# USB.net
KiCad netlist of a schematic drawn in EAGLE
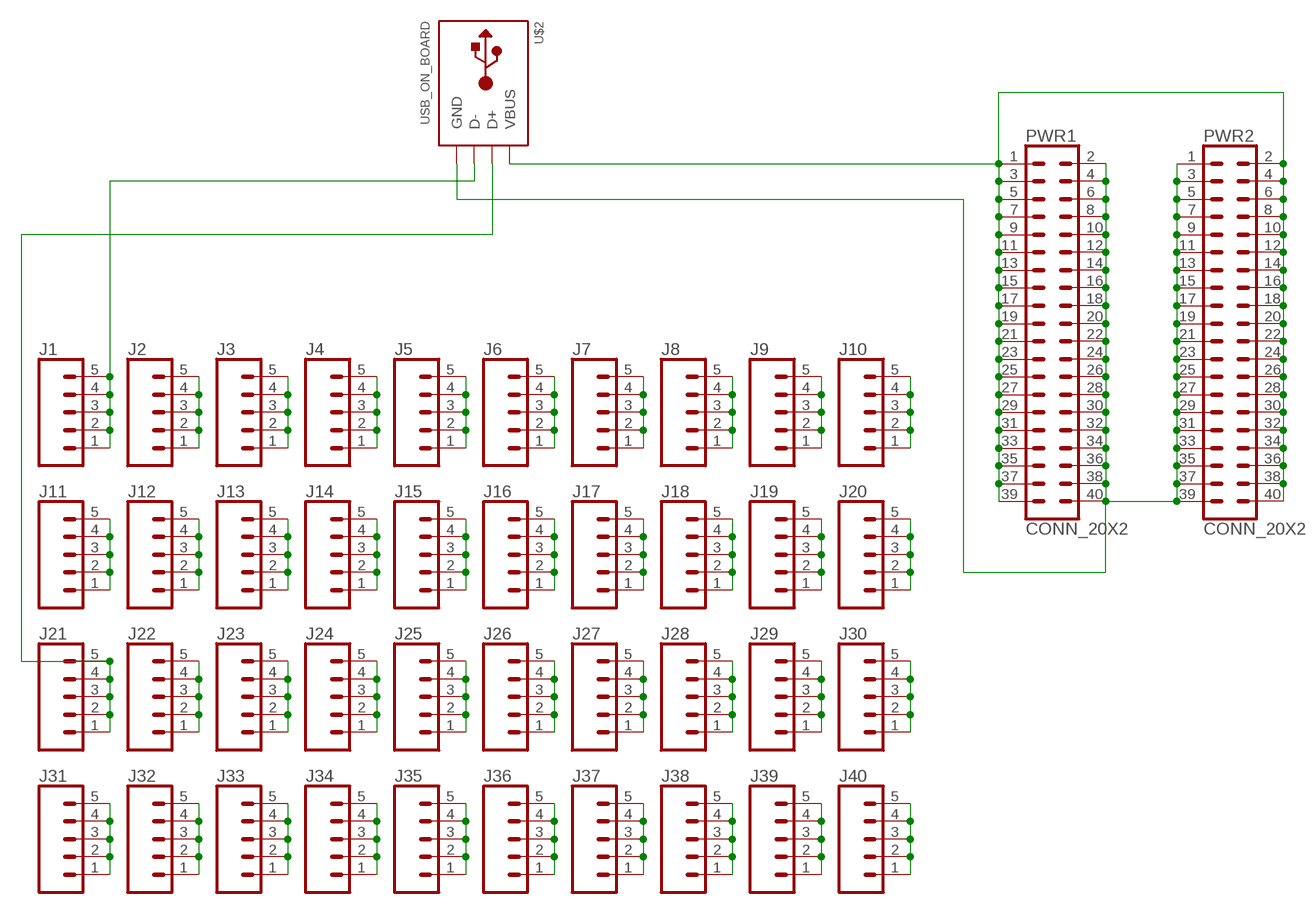
[diagram p0: schematic, sheet 1]

(export (version "E")
  (design (tool "Eeschema 10.0.6"))
  (components
    (comp (ref "J1")
      (value "CONN_05")
      (footprint "eagle-import:1X05")
      (libsource (lib "eagle-import") (part "CONN_05"))
    )
    (comp (ref "J2")
      (value "CONN_05")
      (footprint "eagle-import:1X05")
      (libsource (lib "eagle-import") (part "CONN_05"))
    )
    (comp (ref "J3")
      (value "CONN_05")
      (footprint "eagle-import:1X05")
      (libsource (lib "eagle-import") (part "CONN_05"))
    )
    (comp (ref "J4")
      (value "CONN_05")
      (footprint "eagle-import:1X05")
      (libsource (lib "eagle-import") (part "CONN_05"))
    )
    (comp (ref "J5")
      (value "CONN_05")
      (footprint "eagle-import:1X05")
      (libsource (lib "eagle-import") (part "CONN_05"))
    )
    (comp (ref "J6")
      (value "CONN_05")
      (footprint "eagle-import:1X05")
      (libsource (lib "eagle-import") (part "CONN_05"))
    )
    (comp (ref "J7")
      (value "CONN_05")
      (footprint "eagle-import:1X05")
      (libsource (lib "eagle-import") (part "CONN_05"))
    )
    (comp (ref "J8")
      (value "CONN_05")
      (footprint "eagle-import:1X05")
      (libsource (lib "eagle-import") (part "CONN_05"))
    )
    (comp (ref "J9")
      (value "CONN_05")
      (footprint "eagle-import:1X05")
      (libsource (lib "eagle-import") (part "CONN_05"))
    )
    (comp (ref "J10")
      (value "CONN_05")
      (footprint "eagle-import:1X05")
      (libsource (lib "eagle-import") (part "CONN_05"))
    )
    (comp (ref "J11")
      (value "CONN_05")
      (footprint "eagle-import:1X05")
      (libsource (lib "eagle-import") (part "CONN_05"))
    )
    (comp (ref "J12")
      (value "CONN_05")
      (footprint "eagle-import:1X05")
      (libsource (lib "eagle-import") (part "CONN_05"))
    )
    (comp (ref "J13")
      (value "CONN_05")
      (footprint "eagle-import:1X05")
      (libsource (lib "eagle-import") (part "CONN_05"))
    )
    (comp (ref "J14")
      (value "CONN_05")
      (footprint "eagle-import:1X05")
      (libsource (lib "eagle-import") (part "CONN_05"))
    )
    (comp (ref "J15")
      (value "CONN_05")
      (footprint "eagle-import:1X05")
      (libsource (lib "eagle-import") (part "CONN_05"))
    )
    (comp (ref "J16")
      (value "CONN_05")
      (footprint "eagle-import:1X05")
      (libsource (lib "eagle-import") (part "CONN_05"))
    )
    (comp (ref "J17")
      (value "CONN_05")
      (footprint "eagle-import:1X05")
      (libsource (lib "eagle-import") (part "CONN_05"))
    )
    (comp (ref "J18")
      (value "CONN_05")
      (footprint "eagle-import:1X05")
      (libsource (lib "eagle-import") (part "CONN_05"))
    )
    (comp (ref "J19")
      (value "CONN_05")
      (footprint "eagle-import:1X05")
      (libsource (lib "eagle-import") (part "CONN_05"))
    )
    (comp (ref "J20")
      (value "CONN_05")
      (footprint "eagle-import:1X05")
      (libsource (lib "eagle-import") (part "CONN_05"))
    )
    (comp (ref "J21")
      (value "CONN_05")
      (footprint "eagle-import:1X05")
      (libsource (lib "eagle-import") (part "CONN_05"))
    )
    (comp (ref "J22")
      (value "CONN_05")
      (footprint "eagle-import:1X05")
      (libsource (lib "eagle-import") (part "CONN_05"))
    )
    (comp (ref "J23")
      (value "CONN_05")
      (footprint "eagle-import:1X05")
      (libsource (lib "eagle-import") (part "CONN_05"))
    )
    (comp (ref "J24")
      (value "CONN_05")
      (footprint "eagle-import:1X05")
      (libsource (lib "eagle-import") (part "CONN_05"))
    )
    (comp (ref "J25")
      (value "CONN_05")
      (footprint "eagle-import:1X05")
      (libsource (lib "eagle-import") (part "CONN_05"))
    )
    (comp (ref "J26")
      (value "CONN_05")
      (footprint "eagle-import:1X05")
      (libsource (lib "eagle-import") (part "CONN_05"))
    )
    (comp (ref "J27")
      (value "CONN_05")
      (footprint "eagle-import:1X05")
      (libsource (lib "eagle-import") (part "CONN_05"))
    )
    (comp (ref "J28")
      (value "CONN_05")
      (footprint "eagle-import:1X05")
      (libsource (lib "eagle-import") (part "CONN_05"))
    )
    (comp (ref "J29")
      (value "CONN_05")
      (footprint "eagle-import:1X05")
      (libsource (lib "eagle-import") (part "CONN_05"))
    )
    (comp (ref "J30")
      (value "CONN_05")
      (footprint "eagle-import:1X05")
      (libsource (lib "eagle-import") (part "CONN_05"))
    )
    (comp (ref "J31")
      (value "CONN_05")
      (footprint "eagle-import:1X05")
      (libsource (lib "eagle-import") (part "CONN_05"))
    )
    (comp (ref "J32")
      (value "CONN_05")
      (footprint "eagle-import:1X05")
      (libsource (lib "eagle-import") (part "CONN_05"))
    )
    (comp (ref "J33")
      (value "CONN_05")
      (footprint "eagle-import:1X05")
      (libsource (lib "eagle-import") (part "CONN_05"))
    )
    (comp (ref "J34")
      (value "CONN_05")
      (footprint "eagle-import:1X05")
      (libsource (lib "eagle-import") (part "CONN_05"))
    )
    (comp (ref "J35")
      (value "CONN_05")
      (footprint "eagle-import:1X05")
      (libsource (lib "eagle-import") (part "CONN_05"))
    )
    (comp (ref "J36")
      (value "CONN_05")
      (footprint "eagle-import:1X05")
      (libsource (lib "eagle-import") (part "CONN_05"))
    )
    (comp (ref "J37")
      (value "CONN_05")
      (footprint "eagle-import:1X05")
      (libsource (lib "eagle-import") (part "CONN_05"))
    )
    (comp (ref "J38")
      (value "CONN_05")
      (footprint "eagle-import:1X05")
      (libsource (lib "eagle-import") (part "CONN_05"))
    )
    (comp (ref "J39")
      (value "CONN_05")
      (footprint "eagle-import:1X05")
      (libsource (lib "eagle-import") (part "CONN_05"))
    )
    (comp (ref "J40")
      (value "CONN_05")
      (footprint "eagle-import:1X05")
      (libsource (lib "eagle-import") (part "CONN_05"))
    )
    (comp (ref "PWR1")
      (value "CONN_20X2")
      (footprint "eagle-import:2X20")
      (libsource (lib "eagle-import") (part "CONN_20X2"))
    )
    (comp (ref "PWR2")
      (value "CONN_20X2")
      (footprint "eagle-import:2X20")
      (libsource (lib "eagle-import") (part "CONN_20X2"))
    )
    (comp (ref "U$2")
      (value "USB_ON_BOARD")
      (footprint "eagle-import:USB_ON_BOARD")
      (libsource (lib "eagle-import") (part "USB_ON_BOARD"))
    )
  )
  (nets
    (net (code "1") (name "Net-(J1-Pad1)") (class "Default")
      (node (ref "J1") (pin "1") (pinfunction "1_1") (pintype "passive"))
      (node (ref "J1") (pin "2") (pinfunction "2_2") (pintype "passive"))
      (node (ref "J1") (pin "3") (pinfunction "3_3") (pintype "passive"))
      (node (ref "J1") (pin "4") (pinfunction "4_4") (pintype "passive"))
      (node (ref "J1") (pin "5") (pinfunction "5_5") (pintype "passive"))
      (node (ref "U$2") (pin "D-") (pinfunction "D-_D-") (pintype "bidirectional"))
    )
    (net (code "2") (name "Net-(J2-Pad1)") (class "Default")
      (node (ref "J2") (pin "1") (pinfunction "1_1") (pintype "passive"))
      (node (ref "J2") (pin "2") (pinfunction "2_2") (pintype "passive"))
      (node (ref "J2") (pin "3") (pinfunction "3_3") (pintype "passive"))
      (node (ref "J2") (pin "4") (pinfunction "4_4") (pintype "passive"))
      (node (ref "J2") (pin "5") (pinfunction "5_5") (pintype "passive"))
    )
    (net (code "3") (name "Net-(J3-Pad1)") (class "Default")
      (node (ref "J3") (pin "1") (pinfunction "1_1") (pintype "passive"))
      (node (ref "J3") (pin "2") (pinfunction "2_2") (pintype "passive"))
      (node (ref "J3") (pin "3") (pinfunction "3_3") (pintype "passive"))
      (node (ref "J3") (pin "4") (pinfunction "4_4") (pintype "passive"))
      (node (ref "J3") (pin "5") (pinfunction "5_5") (pintype "passive"))
    )
    (net (code "4") (name "Net-(J4-Pad1)") (class "Default")
      (node (ref "J4") (pin "1") (pinfunction "1_1") (pintype "passive"))
      (node (ref "J4") (pin "2") (pinfunction "2_2") (pintype "passive"))
      (node (ref "J4") (pin "3") (pinfunction "3_3") (pintype "passive"))
      (node (ref "J4") (pin "4") (pinfunction "4_4") (pintype "passive"))
      (node (ref "J4") (pin "5") (pinfunction "5_5") (pintype "passive"))
    )
    (net (code "5") (name "Net-(J5-Pad1)") (class "Default")
      (node (ref "J5") (pin "1") (pinfunction "1_1") (pintype "passive"))
      (node (ref "J5") (pin "2") (pinfunction "2_2") (pintype "passive"))
      (node (ref "J5") (pin "3") (pinfunction "3_3") (pintype "passive"))
      (node (ref "J5") (pin "4") (pinfunction "4_4") (pintype "passive"))
      (node (ref "J5") (pin "5") (pinfunction "5_5") (pintype "passive"))
    )
    (net (code "6") (name "Net-(J6-Pad1)") (class "Default")
      (node (ref "J6") (pin "1") (pinfunction "1_1") (pintype "passive"))
      (node (ref "J6") (pin "2") (pinfunction "2_2") (pintype "passive"))
      (node (ref "J6") (pin "3") (pinfunction "3_3") (pintype "passive"))
      (node (ref "J6") (pin "4") (pinfunction "4_4") (pintype "passive"))
      (node (ref "J6") (pin "5") (pinfunction "5_5") (pintype "passive"))
    )
    (net (code "7") (name "Net-(J7-Pad1)") (class "Default")
      (node (ref "J7") (pin "1") (pinfunction "1_1") (pintype "passive"))
      (node (ref "J7") (pin "2") (pinfunction "2_2") (pintype "passive"))
      (node (ref "J7") (pin "3") (pinfunction "3_3") (pintype "passive"))
      (node (ref "J7") (pin "4") (pinfunction "4_4") (pintype "passive"))
      (node (ref "J7") (pin "5") (pinfunction "5_5") (pintype "passive"))
    )
    (net (code "8") (name "Net-(J8-Pad1)") (class "Default")
      (node (ref "J8") (pin "1") (pinfunction "1_1") (pintype "passive"))
      (node (ref "J8") (pin "2") (pinfunction "2_2") (pintype "passive"))
      (node (ref "J8") (pin "3") (pinfunction "3_3") (pintype "passive"))
      (node (ref "J8") (pin "4") (pinfunction "4_4") (pintype "passive"))
      (node (ref "J8") (pin "5") (pinfunction "5_5") (pintype "passive"))
    )
    (net (code "9") (name "Net-(J9-Pad1)") (class "Default")
      (node (ref "J9") (pin "1") (pinfunction "1_1") (pintype "passive"))
      (node (ref "J9") (pin "2") (pinfunction "2_2") (pintype "passive"))
      (node (ref "J9") (pin "3") (pinfunction "3_3") (pintype "passive"))
      (node (ref "J9") (pin "4") (pinfunction "4_4") (pintype "passive"))
      (node (ref "J9") (pin "5") (pinfunction "5_5") (pintype "passive"))
    )
    (net (code "10") (name "Net-(J10-Pad1)") (class "Default")
      (node (ref "J10") (pin "1") (pinfunction "1_1") (pintype "passive"))
      (node (ref "J10") (pin "2") (pinfunction "2_2") (pintype "passive"))
      (node (ref "J10") (pin "3") (pinfunction "3_3") (pintype "passive"))
      (node (ref "J10") (pin "4") (pinfunction "4_4") (pintype "passive"))
      (node (ref "J10") (pin "5") (pinfunction "5_5") (pintype "passive"))
    )
    (net (code "11") (name "Net-(J11-Pad1)") (class "Default")
      (node (ref "J11") (pin "1") (pinfunction "1_1") (pintype "passive"))
      (node (ref "J11") (pin "2") (pinfunction "2_2") (pintype "passive"))
      (node (ref "J11") (pin "3") (pinfunction "3_3") (pintype "passive"))
      (node (ref "J11") (pin "4") (pinfunction "4_4") (pintype "passive"))
      (node (ref "J11") (pin "5") (pinfunction "5_5") (pintype "passive"))
    )
    (net (code "12") (name "Net-(J12-Pad1)") (class "Default")
      (node (ref "J12") (pin "1") (pinfunction "1_1") (pintype "passive"))
      (node (ref "J12") (pin "2") (pinfunction "2_2") (pintype "passive"))
      (node (ref "J12") (pin "3") (pinfunction "3_3") (pintype "passive"))
      (node (ref "J12") (pin "4") (pinfunction "4_4") (pintype "passive"))
      (node (ref "J12") (pin "5") (pinfunction "5_5") (pintype "passive"))
    )
    (net (code "13") (name "Net-(J13-Pad1)") (class "Default")
      (node (ref "J13") (pin "1") (pinfunction "1_1") (pintype "passive"))
      (node (ref "J13") (pin "2") (pinfunction "2_2") (pintype "passive"))
      (node (ref "J13") (pin "3") (pinfunction "3_3") (pintype "passive"))
      (node (ref "J13") (pin "4") (pinfunction "4_4") (pintype "passive"))
      (node (ref "J13") (pin "5") (pinfunction "5_5") (pintype "passive"))
    )
    (net (code "14") (name "Net-(J14-Pad1)") (class "Default")
      (node (ref "J14") (pin "1") (pinfunction "1_1") (pintype "passive"))
      (node (ref "J14") (pin "2") (pinfunction "2_2") (pintype "passive"))
      (node (ref "J14") (pin "3") (pinfunction "3_3") (pintype "passive"))
      (node (ref "J14") (pin "4") (pinfunction "4_4") (pintype "passive"))
      (node (ref "J14") (pin "5") (pinfunction "5_5") (pintype "passive"))
    )
    (net (code "15") (name "Net-(J15-Pad1)") (class "Default")
      (node (ref "J15") (pin "1") (pinfunction "1_1") (pintype "passive"))
      (node (ref "J15") (pin "2") (pinfunction "2_2") (pintype "passive"))
      (node (ref "J15") (pin "3") (pinfunction "3_3") (pintype "passive"))
      (node (ref "J15") (pin "4") (pinfunction "4_4") (pintype "passive"))
      (node (ref "J15") (pin "5") (pinfunction "5_5") (pintype "passive"))
    )
    (net (code "16") (name "Net-(J16-Pad1)") (class "Default")
      (node (ref "J16") (pin "1") (pinfunction "1_1") (pintype "passive"))
      (node (ref "J16") (pin "2") (pinfunction "2_2") (pintype "passive"))
      (node (ref "J16") (pin "3") (pinfunction "3_3") (pintype "passive"))
      (node (ref "J16") (pin "4") (pinfunction "4_4") (pintype "passive"))
      (node (ref "J16") (pin "5") (pinfunction "5_5") (pintype "passive"))
    )
    (net (code "17") (name "Net-(J17-Pad1)") (class "Default")
      (node (ref "J17") (pin "1") (pinfunction "1_1") (pintype "passive"))
      (node (ref "J17") (pin "2") (pinfunction "2_2") (pintype "passive"))
      (node (ref "J17") (pin "3") (pinfunction "3_3") (pintype "passive"))
      (node (ref "J17") (pin "4") (pinfunction "4_4") (pintype "passive"))
      (node (ref "J17") (pin "5") (pinfunction "5_5") (pintype "passive"))
    )
    (net (code "18") (name "Net-(J18-Pad1)") (class "Default")
      (node (ref "J18") (pin "1") (pinfunction "1_1") (pintype "passive"))
      (node (ref "J18") (pin "2") (pinfunction "2_2") (pintype "passive"))
      (node (ref "J18") (pin "3") (pinfunction "3_3") (pintype "passive"))
      (node (ref "J18") (pin "4") (pinfunction "4_4") (pintype "passive"))
      (node (ref "J18") (pin "5") (pinfunction "5_5") (pintype "passive"))
    )
    (net (code "19") (name "Net-(J19-Pad1)") (class "Default")
      (node (ref "J19") (pin "1") (pinfunction "1_1") (pintype "passive"))
      (node (ref "J19") (pin "2") (pinfunction "2_2") (pintype "passive"))
      (node (ref "J19") (pin "3") (pinfunction "3_3") (pintype "passive"))
      (node (ref "J19") (pin "4") (pinfunction "4_4") (pintype "passive"))
      (node (ref "J19") (pin "5") (pinfunction "5_5") (pintype "passive"))
    )
    (net (code "20") (name "Net-(J20-Pad1)") (class "Default")
      (node (ref "J20") (pin "1") (pinfunction "1_1") (pintype "passive"))
      (node (ref "J20") (pin "2") (pinfunction "2_2") (pintype "passive"))
      (node (ref "J20") (pin "3") (pinfunction "3_3") (pintype "passive"))
      (node (ref "J20") (pin "4") (pinfunction "4_4") (pintype "passive"))
      (node (ref "J20") (pin "5") (pinfunction "5_5") (pintype "passive"))
    )
    (net (code "21") (name "Net-(J21-Pad1)") (class "Default")
      (node (ref "J21") (pin "1") (pinfunction "1_1") (pintype "passive"))
      (node (ref "J21") (pin "2") (pinfunction "2_2") (pintype "passive"))
      (node (ref "J21") (pin "3") (pinfunction "3_3") (pintype "passive"))
      (node (ref "J21") (pin "4") (pinfunction "4_4") (pintype "passive"))
      (node (ref "J21") (pin "5") (pinfunction "5_5") (pintype "passive"))
      (node (ref "U$2") (pin "D+") (pinfunction "D+_D+") (pintype "bidirectional"))
    )
    (net (code "22") (name "Net-(J22-Pad1)") (class "Default")
      (node (ref "J22") (pin "1") (pinfunction "1_1") (pintype "passive"))
      (node (ref "J22") (pin "2") (pinfunction "2_2") (pintype "passive"))
      (node (ref "J22") (pin "3") (pinfunction "3_3") (pintype "passive"))
      (node (ref "J22") (pin "4") (pinfunction "4_4") (pintype "passive"))
      (node (ref "J22") (pin "5") (pinfunction "5_5") (pintype "passive"))
    )
    (net (code "23") (name "Net-(J23-Pad1)") (class "Default")
      (node (ref "J23") (pin "1") (pinfunction "1_1") (pintype "passive"))
      (node (ref "J23") (pin "2") (pinfunction "2_2") (pintype "passive"))
      (node (ref "J23") (pin "3") (pinfunction "3_3") (pintype "passive"))
      (node (ref "J23") (pin "4") (pinfunction "4_4") (pintype "passive"))
      (node (ref "J23") (pin "5") (pinfunction "5_5") (pintype "passive"))
    )
    (net (code "24") (name "Net-(J24-Pad1)") (class "Default")
      (node (ref "J24") (pin "1") (pinfunction "1_1") (pintype "passive"))
      (node (ref "J24") (pin "2") (pinfunction "2_2") (pintype "passive"))
      (node (ref "J24") (pin "3") (pinfunction "3_3") (pintype "passive"))
      (node (ref "J24") (pin "4") (pinfunction "4_4") (pintype "passive"))
      (node (ref "J24") (pin "5") (pinfunction "5_5") (pintype "passive"))
    )
    (net (code "25") (name "Net-(J25-Pad1)") (class "Default")
      (node (ref "J25") (pin "1") (pinfunction "1_1") (pintype "passive"))
      (node (ref "J25") (pin "2") (pinfunction "2_2") (pintype "passive"))
      (node (ref "J25") (pin "3") (pinfunction "3_3") (pintype "passive"))
      (node (ref "J25") (pin "4") (pinfunction "4_4") (pintype "passive"))
      (node (ref "J25") (pin "5") (pinfunction "5_5") (pintype "passive"))
    )
    (net (code "26") (name "Net-(J26-Pad1)") (class "Default")
      (node (ref "J26") (pin "1") (pinfunction "1_1") (pintype "passive"))
      (node (ref "J26") (pin "2") (pinfunction "2_2") (pintype "passive"))
      (node (ref "J26") (pin "3") (pinfunction "3_3") (pintype "passive"))
      (node (ref "J26") (pin "4") (pinfunction "4_4") (pintype "passive"))
      (node (ref "J26") (pin "5") (pinfunction "5_5") (pintype "passive"))
    )
    (net (code "27") (name "Net-(J27-Pad1)") (class "Default")
      (node (ref "J27") (pin "1") (pinfunction "1_1") (pintype "passive"))
      (node (ref "J27") (pin "2") (pinfunction "2_2") (pintype "passive"))
      (node (ref "J27") (pin "3") (pinfunction "3_3") (pintype "passive"))
      (node (ref "J27") (pin "4") (pinfunction "4_4") (pintype "passive"))
      (node (ref "J27") (pin "5") (pinfunction "5_5") (pintype "passive"))
    )
    (net (code "28") (name "Net-(J28-Pad1)") (class "Default")
      (node (ref "J28") (pin "1") (pinfunction "1_1") (pintype "passive"))
      (node (ref "J28") (pin "2") (pinfunction "2_2") (pintype "passive"))
      (node (ref "J28") (pin "3") (pinfunction "3_3") (pintype "passive"))
      (node (ref "J28") (pin "4") (pinfunction "4_4") (pintype "passive"))
      (node (ref "J28") (pin "5") (pinfunction "5_5") (pintype "passive"))
    )
    (net (code "29") (name "Net-(J29-Pad1)") (class "Default")
      (node (ref "J29") (pin "1") (pinfunction "1_1") (pintype "passive"))
      (node (ref "J29") (pin "2") (pinfunction "2_2") (pintype "passive"))
      (node (ref "J29") (pin "3") (pinfunction "3_3") (pintype "passive"))
      (node (ref "J29") (pin "4") (pinfunction "4_4") (pintype "passive"))
      (node (ref "J29") (pin "5") (pinfunction "5_5") (pintype "passive"))
    )
    (net (code "30") (name "Net-(J30-Pad1)") (class "Default")
      (node (ref "J30") (pin "1") (pinfunction "1_1") (pintype "passive"))
      (node (ref "J30") (pin "2") (pinfunction "2_2") (pintype "passive"))
      (node (ref "J30") (pin "3") (pinfunction "3_3") (pintype "passive"))
      (node (ref "J30") (pin "4") (pinfunction "4_4") (pintype "passive"))
      (node (ref "J30") (pin "5") (pinfunction "5_5") (pintype "passive"))
    )
    (net (code "31") (name "Net-(J31-Pad1)") (class "Default")
      (node (ref "J31") (pin "1") (pinfunction "1_1") (pintype "passive"))
      (node (ref "J31") (pin "2") (pinfunction "2_2") (pintype "passive"))
      (node (ref "J31") (pin "3") (pinfunction "3_3") (pintype "passive"))
      (node (ref "J31") (pin "4") (pinfunction "4_4") (pintype "passive"))
      (node (ref "J31") (pin "5") (pinfunction "5_5") (pintype "passive"))
    )
    (net (code "32") (name "Net-(J32-Pad1)") (class "Default")
      (node (ref "J32") (pin "1") (pinfunction "1_1") (pintype "passive"))
      (node (ref "J32") (pin "2") (pinfunction "2_2") (pintype "passive"))
      (node (ref "J32") (pin "3") (pinfunction "3_3") (pintype "passive"))
      (node (ref "J32") (pin "4") (pinfunction "4_4") (pintype "passive"))
      (node (ref "J32") (pin "5") (pinfunction "5_5") (pintype "passive"))
    )
    (net (code "33") (name "Net-(J33-Pad1)") (class "Default")
      (node (ref "J33") (pin "1") (pinfunction "1_1") (pintype "passive"))
      (node (ref "J33") (pin "2") (pinfunction "2_2") (pintype "passive"))
      (node (ref "J33") (pin "3") (pinfunction "3_3") (pintype "passive"))
      (node (ref "J33") (pin "4") (pinfunction "4_4") (pintype "passive"))
      (node (ref "J33") (pin "5") (pinfunction "5_5") (pintype "passive"))
    )
    (net (code "34") (name "Net-(J34-Pad1)") (class "Default")
      (node (ref "J34") (pin "1") (pinfunction "1_1") (pintype "passive"))
      (node (ref "J34") (pin "2") (pinfunction "2_2") (pintype "passive"))
      (node (ref "J34") (pin "3") (pinfunction "3_3") (pintype "passive"))
      (node (ref "J34") (pin "4") (pinfunction "4_4") (pintype "passive"))
      (node (ref "J34") (pin "5") (pinfunction "5_5") (pintype "passive"))
    )
    (net (code "35") (name "Net-(J35-Pad1)") (class "Default")
      (node (ref "J35") (pin "1") (pinfunction "1_1") (pintype "passive"))
      (node (ref "J35") (pin "2") (pinfunction "2_2") (pintype "passive"))
      (node (ref "J35") (pin "3") (pinfunction "3_3") (pintype "passive"))
      (node (ref "J35") (pin "4") (pinfunction "4_4") (pintype "passive"))
      (node (ref "J35") (pin "5") (pinfunction "5_5") (pintype "passive"))
    )
    (net (code "36") (name "Net-(J36-Pad1)") (class "Default")
      (node (ref "J36") (pin "1") (pinfunction "1_1") (pintype "passive"))
      (node (ref "J36") (pin "2") (pinfunction "2_2") (pintype "passive"))
      (node (ref "J36") (pin "3") (pinfunction "3_3") (pintype "passive"))
      (node (ref "J36") (pin "4") (pinfunction "4_4") (pintype "passive"))
      (node (ref "J36") (pin "5") (pinfunction "5_5") (pintype "passive"))
    )
    (net (code "37") (name "Net-(J37-Pad1)") (class "Default")
      (node (ref "J37") (pin "1") (pinfunction "1_1") (pintype "passive"))
      (node (ref "J37") (pin "2") (pinfunction "2_2") (pintype "passive"))
      (node (ref "J37") (pin "3") (pinfunction "3_3") (pintype "passive"))
      (node (ref "J37") (pin "4") (pinfunction "4_4") (pintype "passive"))
      (node (ref "J37") (pin "5") (pinfunction "5_5") (pintype "passive"))
    )
    (net (code "38") (name "Net-(J38-Pad1)") (class "Default")
      (node (ref "J38") (pin "1") (pinfunction "1_1") (pintype "passive"))
      (node (ref "J38") (pin "2") (pinfunction "2_2") (pintype "passive"))
      (node (ref "J38") (pin "3") (pinfunction "3_3") (pintype "passive"))
      (node (ref "J38") (pin "4") (pinfunction "4_4") (pintype "passive"))
      (node (ref "J38") (pin "5") (pinfunction "5_5") (pintype "passive"))
    )
    (net (code "39") (name "Net-(J39-Pad1)") (class "Default")
      (node (ref "J39") (pin "1") (pinfunction "1_1") (pintype "passive"))
      (node (ref "J39") (pin "2") (pinfunction "2_2") (pintype "passive"))
      (node (ref "J39") (pin "3") (pinfunction "3_3") (pintype "passive"))
      (node (ref "J39") (pin "4") (pinfunction "4_4") (pintype "passive"))
      (node (ref "J39") (pin "5") (pinfunction "5_5") (pintype "passive"))
    )
    (net (code "40") (name "Net-(J40-Pad1)") (class "Default")
      (node (ref "J40") (pin "1") (pinfunction "1_1") (pintype "passive"))
      (node (ref "J40") (pin "2") (pinfunction "2_2") (pintype "passive"))
      (node (ref "J40") (pin "3") (pinfunction "3_3") (pintype "passive"))
      (node (ref "J40") (pin "4") (pinfunction "4_4") (pintype "passive"))
      (node (ref "J40") (pin "5") (pinfunction "5_5") (pintype "passive"))
    )
    (net (code "41") (name "Net-(PWR1-Pad10)") (class "Default")
      (node (ref "PWR1") (pin "10") (pinfunction "10_10") (pintype "passive"))
      (node (ref "PWR1") (pin "12") (pinfunction "12_12") (pintype "passive"))
      (node (ref "PWR1") (pin "14") (pinfunction "14_14") (pintype "passive"))
      (node (ref "PWR1") (pin "16") (pinfunction "16_16") (pintype "passive"))
      (node (ref "PWR1") (pin "18") (pinfunction "18_18") (pintype "passive"))
      (node (ref "PWR1") (pin "2") (pinfunction "2_2") (pintype "passive"))
      (node (ref "PWR1") (pin "20") (pinfunction "20_20") (pintype "passive"))
      (node (ref "PWR1") (pin "22") (pinfunction "22_22") (pintype "passive"))
      (node (ref "PWR1") (pin "24") (pinfunction "24_24") (pintype "passive"))
      (node (ref "PWR1") (pin "26") (pinfunction "26_26") (pintype "passive"))
      (node (ref "PWR1") (pin "28") (pinfunction "28_28") (pintype "passive"))
      (node (ref "PWR1") (pin "30") (pinfunction "30_30") (pintype "passive"))
      (node (ref "PWR1") (pin "32") (pinfunction "32_32") (pintype "passive"))
      (node (ref "PWR1") (pin "34") (pinfunction "34_34") (pintype "passive"))
      (node (ref "PWR1") (pin "36") (pinfunction "36_36") (pintype "passive"))
      (node (ref "PWR1") (pin "38") (pinfunction "38_38") (pintype "passive"))
      (node (ref "PWR1") (pin "4") (pinfunction "4_4") (pintype "passive"))
      (node (ref "PWR1") (pin "40") (pinfunction "40_40") (pintype "passive"))
      (node (ref "PWR1") (pin "6") (pinfunction "6_6") (pintype "passive"))
      (node (ref "PWR1") (pin "8") (pinfunction "8_8") (pintype "passive"))
      (node (ref "PWR2") (pin "1") (pinfunction "1_1") (pintype "passive"))
      (node (ref "PWR2") (pin "11") (pinfunction "11_11") (pintype "passive"))
      (node (ref "PWR2") (pin "13") (pinfunction "13_13") (pintype "passive"))
      (node (ref "PWR2") (pin "15") (pinfunction "15_15") (pintype "passive"))
      (node (ref "PWR2") (pin "17") (pinfunction "17_17") (pintype "passive"))
      (node (ref "PWR2") (pin "19") (pinfunction "19_19") (pintype "passive"))
      (node (ref "PWR2") (pin "21") (pinfunction "21_21") (pintype "passive"))
      (node (ref "PWR2") (pin "23") (pinfunction "23_23") (pintype "passive"))
      (node (ref "PWR2") (pin "25") (pinfunction "25_25") (pintype "passive"))
      (node (ref "PWR2") (pin "27") (pinfunction "27_27") (pintype "passive"))
      (node (ref "PWR2") (pin "29") (pinfunction "29_29") (pintype "passive"))
      (node (ref "PWR2") (pin "3") (pinfunction "3_3") (pintype "passive"))
      (node (ref "PWR2") (pin "31") (pinfunction "31_31") (pintype "passive"))
      (node (ref "PWR2") (pin "33") (pinfunction "33_33") (pintype "passive"))
      (node (ref "PWR2") (pin "35") (pinfunction "35_35") (pintype "passive"))
      (node (ref "PWR2") (pin "37") (pinfunction "37_37") (pintype "passive"))
      (node (ref "PWR2") (pin "39") (pinfunction "39_39") (pintype "passive"))
      (node (ref "PWR2") (pin "5") (pinfunction "5_5") (pintype "passive"))
      (node (ref "PWR2") (pin "7") (pinfunction "7_7") (pintype "passive"))
      (node (ref "PWR2") (pin "9") (pinfunction "9_9") (pintype "passive"))
      (node (ref "U$2") (pin "GND") (pinfunction "GND_GND") (pintype "power_in"))
    )
    (net (code "42") (name "Net-(U$2-VBUS)") (class "Default")
      (node (ref "PWR1") (pin "1") (pinfunction "1_1") (pintype "passive"))
      (node (ref "PWR1") (pin "11") (pinfunction "11_11") (pintype "passive"))
      (node (ref "PWR1") (pin "13") (pinfunction "13_13") (pintype "passive"))
      (node (ref "PWR1") (pin "15") (pinfunction "15_15") (pintype "passive"))
      (node (ref "PWR1") (pin "17") (pinfunction "17_17") (pintype "passive"))
      (node (ref "PWR1") (pin "19") (pinfunction "19_19") (pintype "passive"))
      (node (ref "PWR1") (pin "21") (pinfunction "21_21") (pintype "passive"))
      (node (ref "PWR1") (pin "23") (pinfunction "23_23") (pintype "passive"))
      (node (ref "PWR1") (pin "25") (pinfunction "25_25") (pintype "passive"))
      (node (ref "PWR1") (pin "27") (pinfunction "27_27") (pintype "passive"))
      (node (ref "PWR1") (pin "29") (pinfunction "29_29") (pintype "passive"))
      (node (ref "PWR1") (pin "3") (pinfunction "3_3") (pintype "passive"))
      (node (ref "PWR1") (pin "31") (pinfunction "31_31") (pintype "passive"))
      (node (ref "PWR1") (pin "33") (pinfunction "33_33") (pintype "passive"))
      (node (ref "PWR1") (pin "35") (pinfunction "35_35") (pintype "passive"))
      (node (ref "PWR1") (pin "37") (pinfunction "37_37") (pintype "passive"))
      (node (ref "PWR1") (pin "39") (pinfunction "39_39") (pintype "passive"))
      (node (ref "PWR1") (pin "5") (pinfunction "5_5") (pintype "passive"))
      (node (ref "PWR1") (pin "7") (pinfunction "7_7") (pintype "passive"))
      (node (ref "PWR1") (pin "9") (pinfunction "9_9") (pintype "passive"))
      (node (ref "PWR2") (pin "10") (pinfunction "10_10") (pintype "passive"))
      (node (ref "PWR2") (pin "12") (pinfunction "12_12") (pintype "passive"))
      (node (ref "PWR2") (pin "14") (pinfunction "14_14") (pintype "passive"))
      (node (ref "PWR2") (pin "16") (pinfunction "16_16") (pintype "passive"))
      (node (ref "PWR2") (pin "18") (pinfunction "18_18") (pintype "passive"))
      (node (ref "PWR2") (pin "2") (pinfunction "2_2") (pintype "passive"))
      (node (ref "PWR2") (pin "20") (pinfunction "20_20") (pintype "passive"))
      (node (ref "PWR2") (pin "22") (pinfunction "22_22") (pintype "passive"))
      (node (ref "PWR2") (pin "24") (pinfunction "24_24") (pintype "passive"))
      (node (ref "PWR2") (pin "26") (pinfunction "26_26") (pintype "passive"))
      (node (ref "PWR2") (pin "28") (pinfunction "28_28") (pintype "passive"))
      (node (ref "PWR2") (pin "30") (pinfunction "30_30") (pintype "passive"))
      (node (ref "PWR2") (pin "32") (pinfunction "32_32") (pintype "passive"))
      (node (ref "PWR2") (pin "34") (pinfunction "34_34") (pintype "passive"))
      (node (ref "PWR2") (pin "36") (pinfunction "36_36") (pintype "passive"))
      (node (ref "PWR2") (pin "38") (pinfunction "38_38") (pintype "passive"))
      (node (ref "PWR2") (pin "4") (pinfunction "4_4") (pintype "passive"))
      (node (ref "PWR2") (pin "40") (pinfunction "40_40") (pintype "passive"))
      (node (ref "PWR2") (pin "6") (pinfunction "6_6") (pintype "passive"))
      (node (ref "PWR2") (pin "8") (pinfunction "8_8") (pintype "passive"))
      (node (ref "U$2") (pin "VCC") (pinfunction "VBUS_VCC") (pintype "power_in"))
    )
  )
)
